# fpc-30-lcd-ERM24064.net
KiCad netlist of a schematic drawn in EAGLE
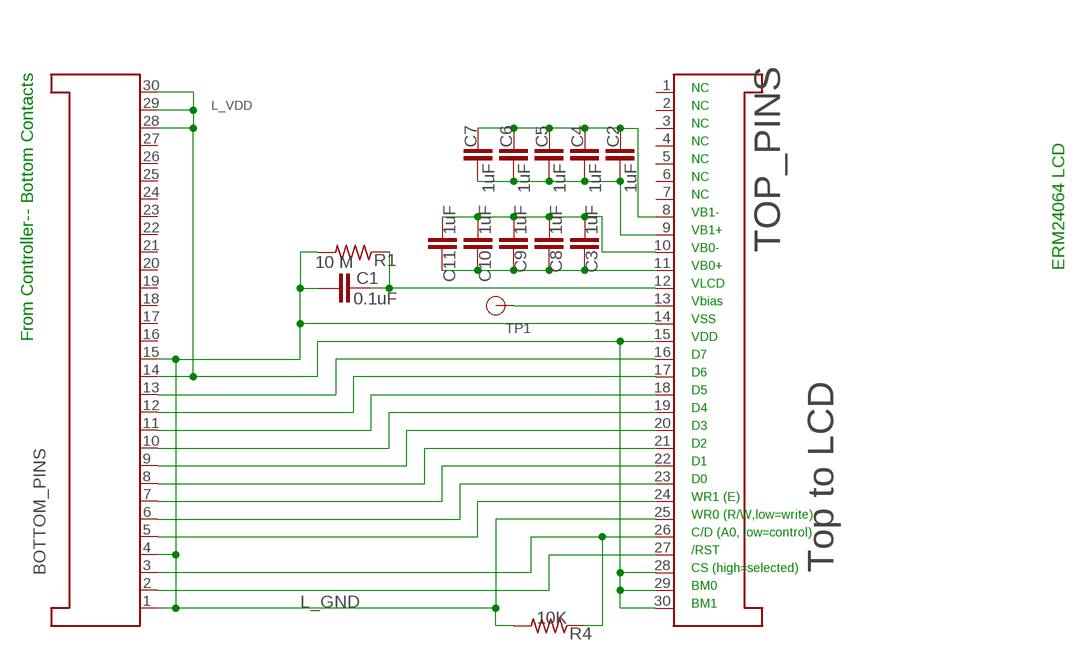
[diagram p0: schematic, sheet 1]

(export (version "E")
  (design (tool "Eeschema 10.0.6"))
  (components
    (comp (ref "BOTTOM_PINS")
      (value "FPC30-bottom_pins")
      (footprint "eagle-import:FH12-30S-0.5SH")
      (libsource (lib "eagle-import") (part "FPC_30-PINS"))
    )
    (comp (ref "C1")
      (value "0.1uF")
      (footprint "eagle-import:C0603K")
      (libsource (lib "eagle-import") (part "C-EUC0603K"))
    )
    (comp (ref "C2")
      (value "1uF")
      (footprint "eagle-import:C0603K")
      (libsource (lib "eagle-import") (part "C-EUC0603K"))
    )
    (comp (ref "C3")
      (value "1uF")
      (footprint "eagle-import:C0603K")
      (libsource (lib "eagle-import") (part "C-EUC0603K"))
    )
    (comp (ref "C4")
      (value "1uF")
      (footprint "eagle-import:C0603K")
      (libsource (lib "eagle-import") (part "C-EUC0603K"))
    )
    (comp (ref "C5")
      (value "1uF")
      (footprint "eagle-import:C0603K")
      (libsource (lib "eagle-import") (part "C-EUC0603K"))
    )
    (comp (ref "C6")
      (value "1uF")
      (footprint "eagle-import:C0603K")
      (libsource (lib "eagle-import") (part "C-EUC0603K"))
    )
    (comp (ref "C7")
      (value "1uF")
      (footprint "eagle-import:C0603K")
      (libsource (lib "eagle-import") (part "C-EUC0603K"))
    )
    (comp (ref "C8")
      (value "1uF")
      (footprint "eagle-import:C0603K")
      (libsource (lib "eagle-import") (part "C-EUC0603K"))
    )
    (comp (ref "C9")
      (value "1uF")
      (footprint "eagle-import:C0603K")
      (libsource (lib "eagle-import") (part "C-EUC0603K"))
    )
    (comp (ref "C10")
      (value "1uF")
      (footprint "eagle-import:C0603K")
      (libsource (lib "eagle-import") (part "C-EUC0603K"))
    )
    (comp (ref "C11")
      (value "1uF")
      (footprint "eagle-import:C0603K")
      (libsource (lib "eagle-import") (part "C-EUC0603K"))
    )
    (comp (ref "R1")
      (value "10 M")
      (footprint "eagle-import:R0603")
      (libsource (lib "eagle-import") (part "R-US_R0603"))
    )
    (comp (ref "R4")
      (value "10K")
      (footprint "eagle-import:R0603")
      (libsource (lib "eagle-import") (part "R-US_R0603"))
    )
    (comp (ref "TOP_PINS")
      (value "Top to LCD")
      (footprint "eagle-import:FH12-30S-0.5SH")
      (libsource (lib "eagle-import") (part "FPC_30-PINS"))
    )
    (comp (ref "TP1")
      (value "TP-1")
      (footprint "eagle-import:TP")
      (libsource (lib "eagle-import") (part "TP-1"))
    )
  )
  (nets
    (net (code "1") (name "/L_GND") (class "Default")
      (node (ref "BOTTOM_PINS") (pin "1") (pinfunction "P$1_1") (pintype "bidirectional"))
      (node (ref "BOTTOM_PINS") (pin "15") (pinfunction "P$15_15") (pintype "bidirectional"))
      (node (ref "BOTTOM_PINS") (pin "4") (pinfunction "P$4_4") (pintype "bidirectional"))
      (node (ref "C1") (pin "2") (pinfunction "2_2") (pintype "passive"))
      (node (ref "R1") (pin "2") (pinfunction "2_2") (pintype "passive"))
      (node (ref "R4") (pin "2") (pinfunction "2_2") (pintype "passive"))
      (node (ref "TOP_PINS") (pin "14") (pinfunction "P$14_14") (pintype "bidirectional"))
      (node (ref "TOP_PINS") (pin "25") (pinfunction "P$25_25") (pintype "bidirectional"))
    )
    (net (code "2") (name "/L_VDD") (class "Default")
      (node (ref "BOTTOM_PINS") (pin "14") (pinfunction "P$14_14") (pintype "bidirectional"))
      (node (ref "BOTTOM_PINS") (pin "28") (pinfunction "P$28_28") (pintype "bidirectional"))
      (node (ref "BOTTOM_PINS") (pin "29") (pinfunction "P$29_29") (pintype "bidirectional"))
      (node (ref "BOTTOM_PINS") (pin "30") (pinfunction "P$30_30") (pintype "bidirectional"))
      (node (ref "TOP_PINS") (pin "15") (pinfunction "P$15_15") (pintype "bidirectional"))
      (node (ref "TOP_PINS") (pin "28") (pinfunction "P$28_28") (pintype "bidirectional"))
      (node (ref "TOP_PINS") (pin "29") (pinfunction "P$29_29") (pintype "bidirectional"))
      (node (ref "TOP_PINS") (pin "30") (pinfunction "P$30_30") (pintype "bidirectional"))
    )
    (net (code "3") (name "Net-(BOTTOM_PINS-P$2)") (class "Default")
      (node (ref "BOTTOM_PINS") (pin "2") (pinfunction "P$2_2") (pintype "bidirectional"))
      (node (ref "TOP_PINS") (pin "27") (pinfunction "P$27_27") (pintype "bidirectional"))
    )
    (net (code "4") (name "Net-(BOTTOM_PINS-P$3)") (class "Default")
      (node (ref "BOTTOM_PINS") (pin "3") (pinfunction "P$3_3") (pintype "bidirectional"))
      (node (ref "R4") (pin "1") (pinfunction "1_1") (pintype "passive"))
      (node (ref "TOP_PINS") (pin "26") (pinfunction "P$26_26") (pintype "bidirectional"))
    )
    (net (code "5") (name "Net-(BOTTOM_PINS-P$5)") (class "Default")
      (node (ref "BOTTOM_PINS") (pin "5") (pinfunction "P$5_5") (pintype "bidirectional"))
      (node (ref "TOP_PINS") (pin "24") (pinfunction "P$24_24") (pintype "bidirectional"))
    )
    (net (code "6") (name "Net-(BOTTOM_PINS-P$6)") (class "Default")
      (node (ref "BOTTOM_PINS") (pin "6") (pinfunction "P$6_6") (pintype "bidirectional"))
      (node (ref "TOP_PINS") (pin "23") (pinfunction "P$23_23") (pintype "bidirectional"))
    )
    (net (code "7") (name "Net-(BOTTOM_PINS-P$7)") (class "Default")
      (node (ref "BOTTOM_PINS") (pin "7") (pinfunction "P$7_7") (pintype "bidirectional"))
      (node (ref "TOP_PINS") (pin "22") (pinfunction "P$22_22") (pintype "bidirectional"))
    )
    (net (code "8") (name "Net-(BOTTOM_PINS-P$8)") (class "Default")
      (node (ref "BOTTOM_PINS") (pin "8") (pinfunction "P$8_8") (pintype "bidirectional"))
      (node (ref "TOP_PINS") (pin "21") (pinfunction "P$21_21") (pintype "bidirectional"))
    )
    (net (code "9") (name "Net-(BOTTOM_PINS-P$9)") (class "Default")
      (node (ref "BOTTOM_PINS") (pin "9") (pinfunction "P$9_9") (pintype "bidirectional"))
      (node (ref "TOP_PINS") (pin "20") (pinfunction "P$20_20") (pintype "bidirectional"))
    )
    (net (code "10") (name "Net-(BOTTOM_PINS-P$10)") (class "Default")
      (node (ref "BOTTOM_PINS") (pin "10") (pinfunction "P$10_10") (pintype "bidirectional"))
      (node (ref "TOP_PINS") (pin "19") (pinfunction "P$19_19") (pintype "bidirectional"))
    )
    (net (code "11") (name "Net-(BOTTOM_PINS-P$11)") (class "Default")
      (node (ref "BOTTOM_PINS") (pin "11") (pinfunction "P$11_11") (pintype "bidirectional"))
      (node (ref "TOP_PINS") (pin "18") (pinfunction "P$18_18") (pintype "bidirectional"))
    )
    (net (code "12") (name "Net-(BOTTOM_PINS-P$12)") (class "Default")
      (node (ref "BOTTOM_PINS") (pin "12") (pinfunction "P$12_12") (pintype "bidirectional"))
      (node (ref "TOP_PINS") (pin "17") (pinfunction "P$17_17") (pintype "bidirectional"))
    )
    (net (code "13") (name "Net-(BOTTOM_PINS-P$13)") (class "Default")
      (node (ref "BOTTOM_PINS") (pin "13") (pinfunction "P$13_13") (pintype "bidirectional"))
      (node (ref "TOP_PINS") (pin "16") (pinfunction "P$16_16") (pintype "bidirectional"))
    )
    (net (code "14") (name "Net-(TOP_PINS-P$8)") (class "Default")
      (node (ref "C2") (pin "1") (pinfunction "1_1") (pintype "passive"))
      (node (ref "C4") (pin "1") (pinfunction "1_1") (pintype "passive"))
      (node (ref "C5") (pin "1") (pinfunction "1_1") (pintype "passive"))
      (node (ref "C6") (pin "1") (pinfunction "1_1") (pintype "passive"))
      (node (ref "C7") (pin "1") (pinfunction "1_1") (pintype "passive"))
      (node (ref "TOP_PINS") (pin "8") (pinfunction "P$8_8") (pintype "bidirectional"))
    )
    (net (code "15") (name "Net-(TOP_PINS-P$9)") (class "Default")
      (node (ref "C2") (pin "2") (pinfunction "2_2") (pintype "passive"))
      (node (ref "C4") (pin "2") (pinfunction "2_2") (pintype "passive"))
      (node (ref "C5") (pin "2") (pinfunction "2_2") (pintype "passive"))
      (node (ref "C6") (pin "2") (pinfunction "2_2") (pintype "passive"))
      (node (ref "C7") (pin "2") (pinfunction "2_2") (pintype "passive"))
      (node (ref "TOP_PINS") (pin "9") (pinfunction "P$9_9") (pintype "bidirectional"))
    )
    (net (code "16") (name "Net-(TOP_PINS-P$10)") (class "Default")
      (node (ref "C10") (pin "2") (pinfunction "2_2") (pintype "passive"))
      (node (ref "C11") (pin "2") (pinfunction "2_2") (pintype "passive"))
      (node (ref "C3") (pin "2") (pinfunction "2_2") (pintype "passive"))
      (node (ref "C8") (pin "2") (pinfunction "2_2") (pintype "passive"))
      (node (ref "C9") (pin "2") (pinfunction "2_2") (pintype "passive"))
      (node (ref "TOP_PINS") (pin "10") (pinfunction "P$10_10") (pintype "bidirectional"))
    )
    (net (code "17") (name "Net-(TOP_PINS-P$11)") (class "Default")
      (node (ref "C10") (pin "1") (pinfunction "1_1") (pintype "passive"))
      (node (ref "C11") (pin "1") (pinfunction "1_1") (pintype "passive"))
      (node (ref "C3") (pin "1") (pinfunction "1_1") (pintype "passive"))
      (node (ref "C8") (pin "1") (pinfunction "1_1") (pintype "passive"))
      (node (ref "C9") (pin "1") (pinfunction "1_1") (pintype "passive"))
      (node (ref "TOP_PINS") (pin "11") (pinfunction "P$11_11") (pintype "bidirectional"))
    )
    (net (code "18") (name "Net-(TOP_PINS-P$12)") (class "Default")
      (node (ref "C1") (pin "1") (pinfunction "1_1") (pintype "passive"))
      (node (ref "R1") (pin "1") (pinfunction "1_1") (pintype "passive"))
      (node (ref "TOP_PINS") (pin "12") (pinfunction "P$12_12") (pintype "bidirectional"))
    )
    (net (code "19") (name "Net-(TOP_PINS-P$13)") (class "Default")
      (node (ref "TOP_PINS") (pin "13") (pinfunction "P$13_13") (pintype "bidirectional"))
      (node (ref "TP1") (pin "P$1") (pinfunction "P$1_P$1") (pintype "bidirectional"))
    )
    (net (code "20") (name "unconnected-(BOTTOM_PINS-P$16-Pad16)") (class "Default")
      (node (ref "BOTTOM_PINS") (pin "16") (pinfunction "P$16_16") (pintype "bidirectional"))
    )
    (net (code "21") (name "unconnected-(BOTTOM_PINS-P$17-Pad17)") (class "Default")
      (node (ref "BOTTOM_PINS") (pin "17") (pinfunction "P$17_17") (pintype "bidirectional"))
    )
    (net (code "22") (name "unconnected-(BOTTOM_PINS-P$18-Pad18)") (class "Default")
      (node (ref "BOTTOM_PINS") (pin "18") (pinfunction "P$18_18") (pintype "bidirectional"))
    )
    (net (code "23") (name "unconnected-(BOTTOM_PINS-P$19-Pad19)") (class "Default")
      (node (ref "BOTTOM_PINS") (pin "19") (pinfunction "P$19_19") (pintype "bidirectional"))
    )
    (net (code "24") (name "unconnected-(BOTTOM_PINS-P$20-Pad20)") (class "Default")
      (node (ref "BOTTOM_PINS") (pin "20") (pinfunction "P$20_20") (pintype "bidirectional"))
    )
    (net (code "25") (name "unconnected-(BOTTOM_PINS-P$21-Pad21)") (class "Default")
      (node (ref "BOTTOM_PINS") (pin "21") (pinfunction "P$21_21") (pintype "bidirectional"))
    )
    (net (code "26") (name "unconnected-(BOTTOM_PINS-P$22-Pad22)") (class "Default")
      (node (ref "BOTTOM_PINS") (pin "22") (pinfunction "P$22_22") (pintype "bidirectional"))
    )
    (net (code "27") (name "unconnected-(BOTTOM_PINS-P$23-Pad23)") (class "Default")
      (node (ref "BOTTOM_PINS") (pin "23") (pinfunction "P$23_23") (pintype "bidirectional"))
    )
    (net (code "28") (name "unconnected-(BOTTOM_PINS-P$24-Pad24)") (class "Default")
      (node (ref "BOTTOM_PINS") (pin "24") (pinfunction "P$24_24") (pintype "bidirectional"))
    )
    (net (code "29") (name "unconnected-(BOTTOM_PINS-P$25-Pad25)") (class "Default")
      (node (ref "BOTTOM_PINS") (pin "25") (pinfunction "P$25_25") (pintype "bidirectional"))
    )
    (net (code "30") (name "unconnected-(BOTTOM_PINS-P$26-Pad26)") (class "Default")
      (node (ref "BOTTOM_PINS") (pin "26") (pinfunction "P$26_26") (pintype "bidirectional"))
    )
    (net (code "31") (name "unconnected-(BOTTOM_PINS-P$27-Pad27)") (class "Default")
      (node (ref "BOTTOM_PINS") (pin "27") (pinfunction "P$27_27") (pintype "bidirectional"))
    )
    (net (code "32") (name "unconnected-(TOP_PINS-P$1-Pad1)") (class "Default")
      (node (ref "TOP_PINS") (pin "1") (pinfunction "P$1_1") (pintype "bidirectional"))
    )
    (net (code "33") (name "unconnected-(TOP_PINS-P$2-Pad2)") (class "Default")
      (node (ref "TOP_PINS") (pin "2") (pinfunction "P$2_2") (pintype "bidirectional"))
    )
    (net (code "34") (name "unconnected-(TOP_PINS-P$3-Pad3)") (class "Default")
      (node (ref "TOP_PINS") (pin "3") (pinfunction "P$3_3") (pintype "bidirectional"))
    )
    (net (code "35") (name "unconnected-(TOP_PINS-P$4-Pad4)") (class "Default")
      (node (ref "TOP_PINS") (pin "4") (pinfunction "P$4_4") (pintype "bidirectional"))
    )
    (net (code "36") (name "unconnected-(TOP_PINS-P$5-Pad5)") (class "Default")
      (node (ref "TOP_PINS") (pin "5") (pinfunction "P$5_5") (pintype "bidirectional"))
    )
    (net (code "37") (name "unconnected-(TOP_PINS-P$6-Pad6)") (class "Default")
      (node (ref "TOP_PINS") (pin "6") (pinfunction "P$6_6") (pintype "bidirectional"))
    )
    (net (code "38") (name "unconnected-(TOP_PINS-P$7-Pad7)") (class "Default")
      (node (ref "TOP_PINS") (pin "7") (pinfunction "P$7_7") (pintype "bidirectional"))
    )
  )
)
